# humidity.net
KiCad netlist of a schematic drawn in Altium Designer
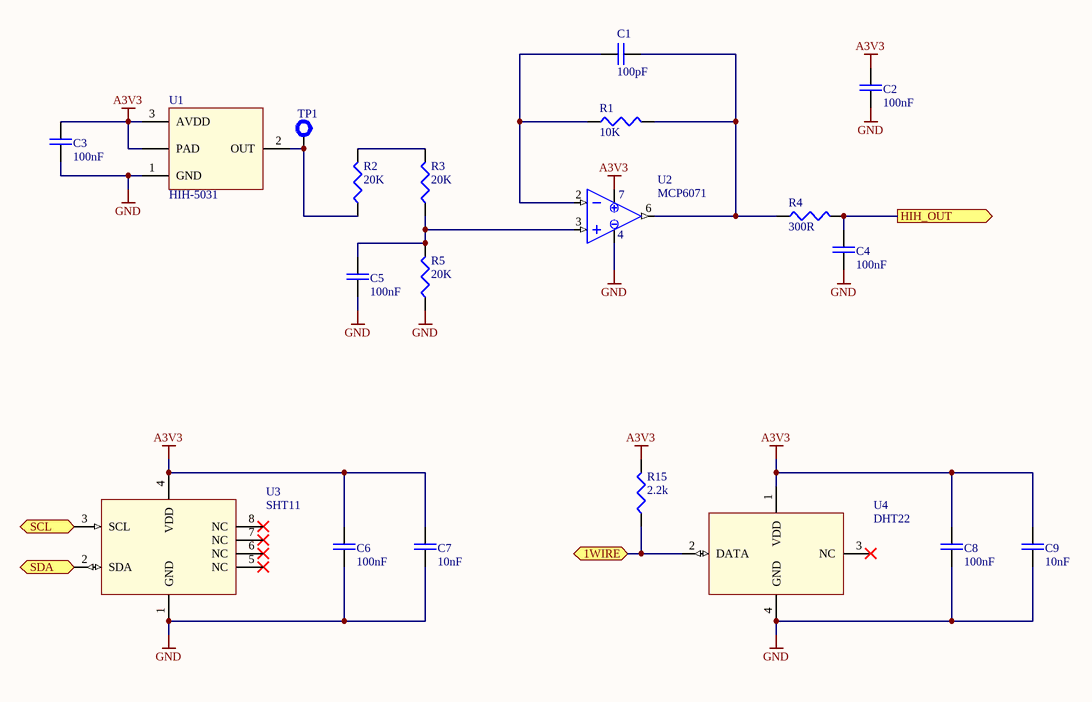
[diagram p0: humidity.SchDoc]

(export (version "E")
  (design (tool "Eeschema 10.0.6"))
  (components
    (comp (ref "C1")
      (value "100pF")
      (footprint "0603")
      (description "Capacitor")
      (fields (field (name "OWNER") "Nuno Brum"))
      (libsource (lib "Alcetronics_Devices") (part "CAP"))
    )
    (comp (ref "C2")
      (value "100nF")
      (footprint "0603")
      (description "Capacitor")
      (fields (field (name "OWNER") "Nuno Brum"))
      (libsource (lib "Alcetronics_Devices") (part "CAP"))
    )
    (comp (ref "C3")
      (value "100nF")
      (footprint "0603")
      (description "Capacitor")
      (fields (field (name "OWNER") "Nuno Brum"))
      (libsource (lib "Alcetronics_Devices") (part "CAP"))
    )
    (comp (ref "C4")
      (value "100nF")
      (footprint "0603")
      (description "Capacitor")
      (fields (field (name "OWNER") "Nuno Brum"))
      (libsource (lib "Alcetronics_Devices") (part "CAP"))
    )
    (comp (ref "C5")
      (value "100nF")
      (footprint "0603")
      (description "Capacitor")
      (fields (field (name "OWNER") "Nuno Brum"))
      (libsource (lib "Alcetronics_Devices") (part "CAP"))
    )
    (comp (ref "C6")
      (value "100nF")
      (footprint "0603")
      (description "Capacitor")
      (fields (field (name "OWNER") "Nuno Brum"))
      (libsource (lib "Alcetronics_Devices") (part "CAP"))
    )
    (comp (ref "C7")
      (value "10nF")
      (footprint "0603")
      (description "Capacitor")
      (fields (field (name "OWNER") "Nuno Brum"))
      (libsource (lib "Alcetronics_Devices") (part "CAP"))
    )
    (comp (ref "C8")
      (value "100nF")
      (footprint "0603")
      (description "Capacitor")
      (fields (field (name "OWNER") "Nuno Brum"))
      (libsource (lib "Alcetronics_Devices") (part "CAP"))
    )
    (comp (ref "C9")
      (value "10nF")
      (footprint "0603")
      (description "Capacitor")
      (fields (field (name "OWNER") "Nuno Brum"))
      (libsource (lib "Alcetronics_Devices") (part "CAP"))
    )
    (comp (ref "R1")
      (value "10K")
      (footprint "0603")
      (description "Resistor")
      (fields (field (name "OWNER") "Nuno Brum"))
      (libsource (lib "Alcetronics_Devices") (part "RES"))
    )
    (comp (ref "R2")
      (value "20K")
      (footprint "0603")
      (description "Resistor")
      (fields (field (name "OWNER") "Nuno Brum"))
      (libsource (lib "Alcetronics_Devices") (part "RES"))
    )
    (comp (ref "R3")
      (value "20K")
      (footprint "0603")
      (description "Resistor")
      (fields (field (name "OWNER") "Nuno Brum"))
      (libsource (lib "Alcetronics_Devices") (part "RES"))
    )
    (comp (ref "R4")
      (value "300R")
      (footprint "0603")
      (description "Resistor")
      (fields (field (name "OWNER") "Nuno Brum"))
      (libsource (lib "Alcetronics_Devices") (part "RES"))
    )
    (comp (ref "R5")
      (value "20K")
      (footprint "0603")
      (description "Resistor")
      (fields (field (name "OWNER") "Nuno Brum"))
      (libsource (lib "Alcetronics_Devices") (part "RES"))
    )
    (comp (ref "R15")
      (value "2.2k")
      (footprint "0603")
      (description "Resistor")
      (fields (field (name "OWNER") "Nuno Brum"))
      (libsource (lib "Alcetronics_Devices") (part "RES"))
    )
    (comp (ref "TP1")
      (value "Test Point")
      (footprint "TERMINAL")
      (description "Test/Probe Point")
      (fields (field (name "OWNER") "Nuno Brum"))
      (libsource (lib "Alcetronics_EM") (part "TEST-PROBE"))
    )
    (comp (ref "U1")
      (value "HIH-5031")
      (footprint "HIH")
      (description "Low Voltage Humidity Sensor")
      (libsource (lib "Alcetronics_IC") (part "HIH-5031"))
    )
    (comp (ref "U2")
      (value "MCP6071")
      (footprint "SOIC-8")
      (description "Low-Offset Opamp")
      (libsource (lib "Alcetronics_IC") (part "MCP6V26"))
    )
    (comp (ref "U3")
      (value "SHT11")
      (footprint "SHT")
      (description "Digital Humidity and Temperature Sensor")
      (libsource (lib "Alcetronics_IC") (part "SHT11"))
    )
    (comp (ref "U4")
      (value "DHT22")
      (footprint "DHT22")
      (description "Digital Humidity and Temperature Sensor")
      (libsource (lib "Alcetronics_IC") (part "DHT22"))
    )
  )
  (nets
    (net (code "1") (name "/1WIRE") (class "Default")
      (node (ref "R15") (pin "1") (pinfunction "1_1") (pintype "passive"))
      (node (ref "U4") (pin "2") (pinfunction "DATA_2") (pintype "bidirectional"))
    )
    (net (code "2") (name "/HIH_OUT") (class "Default")
      (node (ref "C4") (pin "2") (pinfunction "2_2") (pintype "passive"))
      (node (ref "R4") (pin "2") (pinfunction "2_2") (pintype "passive"))
    )
    (net (code "3") (name "/SCL") (class "Default")
      (node (ref "U3") (pin "3") (pinfunction "SCL_3") (pintype "input"))
    )
    (net (code "4") (name "/SDA") (class "Default")
      (node (ref "U3") (pin "2") (pinfunction "SDA_2") (pintype "bidirectional"))
    )
    (net (code "5") (name "A3V3") (class "Default")
      (node (ref "C2") (pin "2") (pinfunction "2_2") (pintype "passive"))
      (node (ref "C3") (pin "2") (pinfunction "2_2") (pintype "passive"))
      (node (ref "C6") (pin "2") (pinfunction "2_2") (pintype "passive"))
      (node (ref "C7") (pin "2") (pinfunction "2_2") (pintype "passive"))
      (node (ref "C8") (pin "2") (pinfunction "2_2") (pintype "passive"))
      (node (ref "C9") (pin "2") (pinfunction "2_2") (pintype "passive"))
      (node (ref "R15") (pin "2") (pinfunction "2_2") (pintype "passive"))
      (node (ref "U1") (pin "3") (pinfunction "AVDD_3") (pintype "power_in"))
      (node (ref "U1") (pin "PAD") (pinfunction "PAD_PAD") (pintype "passive"))
      (node (ref "U2") (pin "7") (pinfunction "VDD_7") (pintype "power_in"))
      (node (ref "U3") (pin "4") (pinfunction "VDD_4") (pintype "power_in"))
      (node (ref "U4") (pin "1") (pinfunction "VDD_1") (pintype "power_in"))
    )
    (net (code "6") (name "GND") (class "Default")
      (node (ref "C2") (pin "1") (pinfunction "1_1") (pintype "passive"))
      (node (ref "C3") (pin "1") (pinfunction "1_1") (pintype "passive"))
      (node (ref "C4") (pin "1") (pinfunction "1_1") (pintype "passive"))
      (node (ref "C5") (pin "1") (pinfunction "1_1") (pintype "passive"))
      (node (ref "C6") (pin "1") (pinfunction "1_1") (pintype "passive"))
      (node (ref "C7") (pin "1") (pinfunction "1_1") (pintype "passive"))
      (node (ref "C8") (pin "1") (pinfunction "1_1") (pintype "passive"))
      (node (ref "C9") (pin "1") (pinfunction "1_1") (pintype "passive"))
      (node (ref "R5") (pin "1") (pinfunction "1_1") (pintype "passive"))
      (node (ref "U1") (pin "1") (pinfunction "GND_1") (pintype "power_in"))
      (node (ref "U2") (pin "4") (pinfunction "VSS_4") (pintype "power_in"))
      (node (ref "U3") (pin "1") (pinfunction "GND_1") (pintype "power_in"))
      (node (ref "U4") (pin "4") (pinfunction "GND_4") (pintype "power_in"))
    )
    (net (code "7") (name "Net-(R2-Pad2)") (class "Default")
      (node (ref "R2") (pin "2") (pinfunction "2_2") (pintype "passive"))
      (node (ref "R3") (pin "2") (pinfunction "2_2") (pintype "passive"))
    )
    (net (code "8") (name "Net-(TP1-TP)") (class "Default")
      (node (ref "R2") (pin "1") (pinfunction "1_1") (pintype "passive"))
      (node (ref "TP1") (pin "1") (pinfunction "TP_1") (pintype "passive"))
      (node (ref "U1") (pin "2") (pinfunction "OUT_2") (pintype "passive"))
    )
    (net (code "9") (name "Net-(U2-INN)") (class "Default")
      (node (ref "C1") (pin "1") (pinfunction "1_1") (pintype "passive"))
      (node (ref "R1") (pin "1") (pinfunction "1_1") (pintype "passive"))
      (node (ref "U2") (pin "2") (pinfunction "INN_2") (pintype "input"))
    )
    (net (code "10") (name "Net-(U2-INP)") (class "Default")
      (node (ref "C5") (pin "2") (pinfunction "2_2") (pintype "passive"))
      (node (ref "R3") (pin "1") (pinfunction "1_1") (pintype "passive"))
      (node (ref "R5") (pin "2") (pinfunction "2_2") (pintype "passive"))
      (node (ref "U2") (pin "3") (pinfunction "INP_3") (pintype "input"))
    )
    (net (code "11") (name "Net-(U2-VOUT)") (class "Default")
      (node (ref "C1") (pin "2") (pinfunction "2_2") (pintype "passive"))
      (node (ref "R1") (pin "2") (pinfunction "2_2") (pintype "passive"))
      (node (ref "R4") (pin "1") (pinfunction "1_1") (pintype "passive"))
      (node (ref "U2") (pin "6") (pinfunction "VOUT_6") (pintype "output"))
    )
    (net (code "12") (name "unconnected-(U3-NC-Pad5)") (class "Default")
      (node (ref "U3") (pin "5") (pinfunction "NC_5") (pintype "passive+no_connect"))
    )
    (net (code "13") (name "unconnected-(U3-NC-Pad6)") (class "Default")
      (node (ref "U3") (pin "6") (pinfunction "NC_6") (pintype "passive+no_connect"))
    )
    (net (code "14") (name "unconnected-(U3-NC-Pad7)") (class "Default")
      (node (ref "U3") (pin "7") (pinfunction "NC_7") (pintype "passive+no_connect"))
    )
    (net (code "15") (name "unconnected-(U3-NC-Pad8)") (class "Default")
      (node (ref "U3") (pin "8") (pinfunction "NC_8") (pintype "passive+no_connect"))
    )
    (net (code "16") (name "unconnected-(U4-NC-Pad3)") (class "Default")
      (node (ref "U4") (pin "3") (pinfunction "NC_3") (pintype "power_in+no_connect"))
    )
  )
)
